# transistor.net
KiCad netlist of a schematic drawn in EAGLE
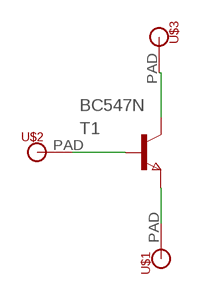
[diagram p0: schematic, sheet 1]

(export (version "E")
  (design (tool "Eeschema 10.0.6"))
  (components
    (comp (ref "T1")
      (value "BC547N")
      (footprint "eagle-import:TO92")
      (fields (field (name "MF") "ON Semiconductor") (field (name "MP") "BC547"))
      (libsource (lib "eagle-import") (part "BC547N"))
    )
    (comp (ref "U$1")
      (value "MICROBIT_PAD")
      (footprint "eagle-import:MICROBIT_PAD")
      (libsource (lib "eagle-import") (part "MICROBIT_PAD"))
    )
    (comp (ref "U$2")
      (value "MICROBIT_PAD")
      (footprint "eagle-import:MICROBIT_PAD")
      (libsource (lib "eagle-import") (part "MICROBIT_PAD"))
    )
    (comp (ref "U$3")
      (value "MICROBIT_PAD")
      (footprint "eagle-import:MICROBIT_PAD")
      (libsource (lib "eagle-import") (part "MICROBIT_PAD"))
    )
  )
  (nets
    (net (code "1") (name "Net-(T1-B)") (class "Default")
      (node (ref "T1") (pin "2") (pinfunction "B_2") (pintype "passive"))
      (node (ref "U$2") (pin "PAD") (pinfunction "P$1_PAD") (pintype "bidirectional"))
    )
    (net (code "2") (name "Net-(T1-C)") (class "Default")
      (node (ref "T1") (pin "1") (pinfunction "C_1") (pintype "passive"))
      (node (ref "U$3") (pin "PAD") (pinfunction "P$1_PAD") (pintype "bidirectional"))
    )
    (net (code "3") (name "Net-(T1-E)") (class "Default")
      (node (ref "T1") (pin "3") (pinfunction "E_3") (pintype "passive"))
      (node (ref "U$1") (pin "PAD") (pinfunction "P$1_PAD") (pintype "bidirectional"))
    )
  )
)
